# HS-Treiber.net
KiCad netlist of a schematic drawn in Altium Designer
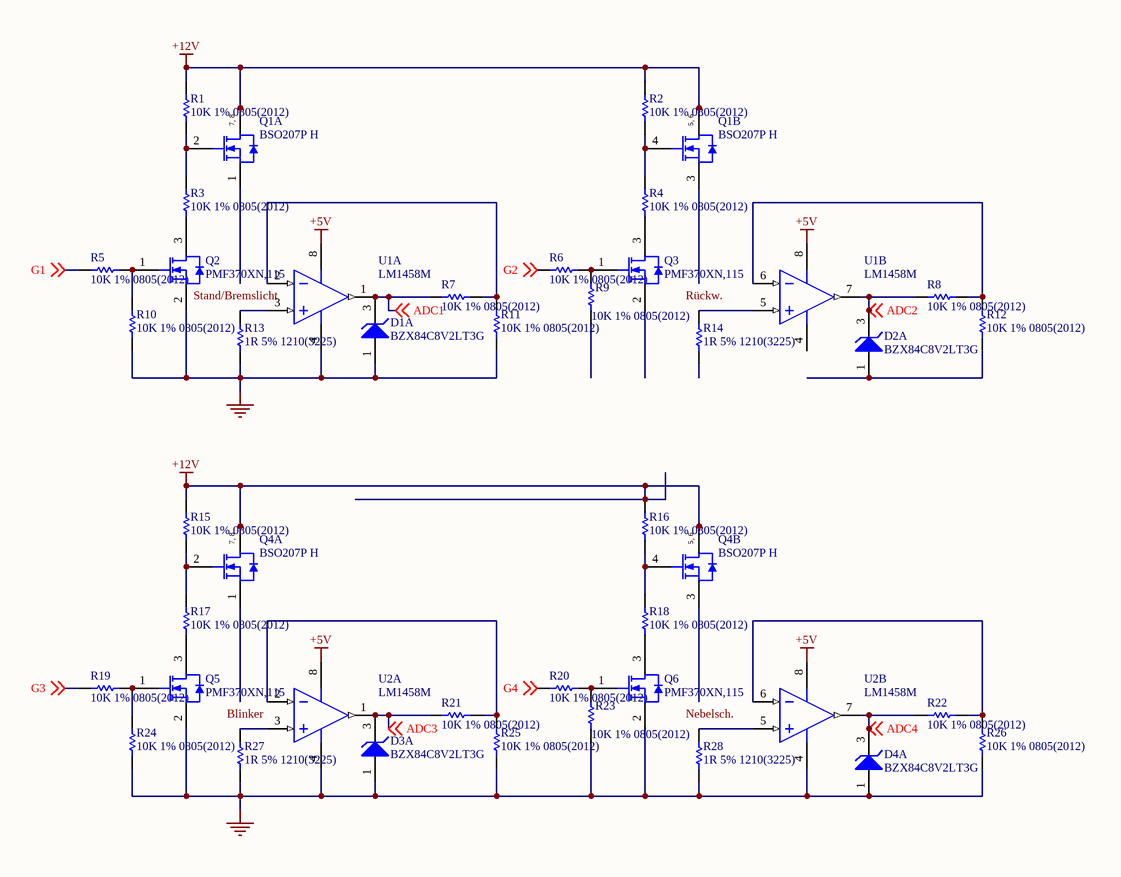
[diagram p0: HS-Treiber.SchDoc]

(export (version "E")
  (design (tool "Eeschema 10.0.6"))
  (components
    (comp (ref "D1")
      (value "BZX84C8V2LT3G")
      (footprint "ONSC-SOT-23-3-318-08_V")
      (description "Zener Voltage Regulator, 225 mW, 3-Pin SOT-23, Pb-Free, Tape and Reel")
      (fields (field (name "MANUFACTURER") "On Semiconductor"))
      (libsource (lib "Altium Content Vault") (part "ONSC-A1K3-3"))
    )
    (comp (ref "D2")
      (value "BZX84C8V2LT3G")
      (footprint "ONSC-SOT-23-3-318-08_V")
      (description "Zener Voltage Regulator, 225 mW, 3-Pin SOT-23, Pb-Free, Tape and Reel")
      (fields (field (name "MANUFACTURER") "On Semiconductor"))
      (libsource (lib "Altium Content Vault") (part "ONSC-A1K3-3"))
    )
    (comp (ref "D3")
      (value "BZX84C8V2LT3G")
      (footprint "ONSC-SOT-23-3-318-08_V")
      (description "Zener Voltage Regulator, 225 mW, 3-Pin SOT-23, Pb-Free, Tape and Reel")
      (fields (field (name "MANUFACTURER") "On Semiconductor"))
      (libsource (lib "Altium Content Vault") (part "ONSC-A1K3-3"))
    )
    (comp (ref "D4")
      (value "BZX84C8V2LT3G")
      (footprint "ONSC-SOT-23-3-318-08_V")
      (description "Zener Voltage Regulator, 225 mW, 3-Pin SOT-23, Pb-Free, Tape and Reel")
      (fields (field (name "MANUFACTURER") "On Semiconductor"))
      (libsource (lib "Altium Content Vault") (part "ONSC-A1K3-3"))
    )
    (comp (ref "Q1")
      (value "BSO207P H")
      (footprint "INF-PG-DSO-8-3_L")
      (fields (field (name "MANUFACTURER") "Infineon"))
      (libsource (lib "Altium Content Vault") (part "INF-MOS-BSXXX-8"))
    )
    (comp (ref "Q2")
      (value "PMF370XN,115")
      (footprint "NXP-SOT323_M")
      (description "N-Channel TrenchMOS Extremely Low Level FET, 30 V, 0.87 A, 3-Pin SOT323, Tape and Reel")
      (fields (field (name "MANUFACTURER") "NXP Semiconductors"))
      (libsource (lib "Altium Content Vault") (part "NXP-NMOS-GSD-3_B"))
    )
    (comp (ref "Q3")
      (value "PMF370XN,115")
      (footprint "NXP-SOT323_M")
      (description "N-Channel TrenchMOS Extremely Low Level FET, 30 V, 0.87 A, 3-Pin SOT323, Tape and Reel")
      (fields (field (name "MANUFACTURER") "NXP Semiconductors"))
      (libsource (lib "Altium Content Vault") (part "NXP-NMOS-GSD-3_B"))
    )
    (comp (ref "Q4")
      (value "BSO207P H")
      (footprint "INF-PG-DSO-8-3_L")
      (fields (field (name "MANUFACTURER") "Infineon"))
      (libsource (lib "Altium Content Vault") (part "INF-MOS-BSXXX-8"))
    )
    (comp (ref "Q5")
      (value "PMF370XN,115")
      (footprint "NXP-SOT323_M")
      (description "N-Channel TrenchMOS Extremely Low Level FET, 30 V, 0.87 A, 3-Pin SOT323, Tape and Reel")
      (fields (field (name "MANUFACTURER") "NXP Semiconductors"))
      (libsource (lib "Altium Content Vault") (part "NXP-NMOS-GSD-3_B"))
    )
    (comp (ref "Q6")
      (value "PMF370XN,115")
      (footprint "NXP-SOT323_M")
      (description "N-Channel TrenchMOS Extremely Low Level FET, 30 V, 0.87 A, 3-Pin SOT323, Tape and Reel")
      (fields (field (name "MANUFACTURER") "NXP Semiconductors"))
      (libsource (lib "Altium Content Vault") (part "NXP-NMOS-GSD-3_B"))
    )
    (comp (ref "R1")
      (value "10K 1% 0805(2012)")
      (footprint "RESC0805(2012)_M")
      (description "10K 0.125W 1% 0805 (2012 Metric)  SMD")
      (fields (field (name "TOLERANCE") "1 %") (field (name "POWER") "0.125 W"))
      (libsource (lib "Altium Content Vault") (part "RES"))
    )
    (comp (ref "R2")
      (value "10K 1% 0805(2012)")
      (footprint "RESC0805(2012)_M")
      (description "10K 0.125W 1% 0805 (2012 Metric)  SMD")
      (fields (field (name "TOLERANCE") "1 %") (field (name "POWER") "0.125 W"))
      (libsource (lib "Altium Content Vault") (part "RES"))
    )
    (comp (ref "R3")
      (value "10K 1% 0805(2012)")
      (footprint "RESC0805(2012)_M")
      (description "10K 0.125W 1% 0805 (2012 Metric)  SMD")
      (fields (field (name "TOLERANCE") "1 %") (field (name "POWER") "0.125 W"))
      (libsource (lib "Altium Content Vault") (part "RES"))
    )
    (comp (ref "R4")
      (value "10K 1% 0805(2012)")
      (footprint "RESC0805(2012)_M")
      (description "10K 0.125W 1% 0805 (2012 Metric)  SMD")
      (fields (field (name "TOLERANCE") "1 %") (field (name "POWER") "0.125 W"))
      (libsource (lib "Altium Content Vault") (part "RES"))
    )
    (comp (ref "R5")
      (value "10K 1% 0805(2012)")
      (footprint "RESC0805(2012)_M")
      (description "10K 0.125W 1% 0805 (2012 Metric)  SMD")
      (fields (field (name "TOLERANCE") "1 %") (field (name "POWER") "0.125 W"))
      (libsource (lib "Altium Content Vault") (part "RES"))
    )
    (comp (ref "R6")
      (value "10K 1% 0805(2012)")
      (footprint "RESC0805(2012)_M")
      (description "10K 0.125W 1% 0805 (2012 Metric)  SMD")
      (fields (field (name "TOLERANCE") "1 %") (field (name "POWER") "0.125 W"))
      (libsource (lib "Altium Content Vault") (part "RES"))
    )
    (comp (ref "R7")
      (value "10K 1% 0805(2012)")
      (footprint "RESC0805(2012)_M")
      (description "10K 0.125W 1% 0805 (2012 Metric)  SMD")
      (fields (field (name "TOLERANCE") "1 %") (field (name "POWER") "0.125 W"))
      (libsource (lib "Altium Content Vault") (part "RES"))
    )
    (comp (ref "R8")
      (value "10K 1% 0805(2012)")
      (footprint "RESC0805(2012)_M")
      (description "10K 0.125W 1% 0805 (2012 Metric)  SMD")
      (fields (field (name "TOLERANCE") "1 %") (field (name "POWER") "0.125 W"))
      (libsource (lib "Altium Content Vault") (part "RES"))
    )
    (comp (ref "R9")
      (value "10K 1% 0805(2012)")
      (footprint "RESC0805(2012)_M")
      (description "10K 0.125W 1% 0805 (2012 Metric)  SMD")
      (fields (field (name "TOLERANCE") "1 %") (field (name "POWER") "0.125 W"))
      (libsource (lib "Altium Content Vault") (part "RES"))
    )
    (comp (ref "R10")
      (value "10K 1% 0805(2012)")
      (footprint "RESC0805(2012)_M")
      (description "10K 0.125W 1% 0805 (2012 Metric)  SMD")
      (fields (field (name "TOLERANCE") "1 %") (field (name "POWER") "0.125 W"))
      (libsource (lib "Altium Content Vault") (part "RES"))
    )
    (comp (ref "R11")
      (value "10K 1% 0805(2012)")
      (footprint "RESC0805(2012)_M")
      (description "10K 0.125W 1% 0805 (2012 Metric)  SMD")
      (fields (field (name "TOLERANCE") "1 %") (field (name "POWER") "0.125 W"))
      (libsource (lib "Altium Content Vault") (part "RES"))
    )
    (comp (ref "R12")
      (value "10K 1% 0805(2012)")
      (footprint "RESC0805(2012)_M")
      (description "10K 0.125W 1% 0805 (2012 Metric)  SMD")
      (fields (field (name "TOLERANCE") "1 %") (field (name "POWER") "0.125 W"))
      (libsource (lib "Altium Content Vault") (part "RES"))
    )
    (comp (ref "R13")
      (value "1R 5% 1210(3225)")
      (footprint "RESC1210(3225)_N")
      (description "1R 0.5W 5% 1210 (3225 Metric)  SMD")
      (fields (field (name "POWER") "0.5 W") (field (name "TOLERANCE") "5 %"))
      (libsource (lib "Altium Content Vault") (part "RES"))
    )
    (comp (ref "R14")
      (value "1R 5% 1210(3225)")
      (footprint "RESC1210(3225)_N")
      (description "1R 0.5W 5% 1210 (3225 Metric)  SMD")
      (fields (field (name "POWER") "0.5 W") (field (name "TOLERANCE") "5 %"))
      (libsource (lib "Altium Content Vault") (part "RES"))
    )
    (comp (ref "R15")
      (value "10K 1% 0805(2012)")
      (footprint "RESC0805(2012)_M")
      (description "10K 0.125W 1% 0805 (2012 Metric)  SMD")
      (fields (field (name "TOLERANCE") "1 %") (field (name "POWER") "0.125 W"))
      (libsource (lib "Altium Content Vault") (part "RES"))
    )
    (comp (ref "R16")
      (value "10K 1% 0805(2012)")
      (footprint "RESC0805(2012)_M")
      (description "10K 0.125W 1% 0805 (2012 Metric)  SMD")
      (fields (field (name "TOLERANCE") "1 %") (field (name "POWER") "0.125 W"))
      (libsource (lib "Altium Content Vault") (part "RES"))
    )
    (comp (ref "R17")
      (value "10K 1% 0805(2012)")
      (footprint "RESC0805(2012)_M")
      (description "10K 0.125W 1% 0805 (2012 Metric)  SMD")
      (fields (field (name "TOLERANCE") "1 %") (field (name "POWER") "0.125 W"))
      (libsource (lib "Altium Content Vault") (part "RES"))
    )
    (comp (ref "R18")
      (value "10K 1% 0805(2012)")
      (footprint "RESC0805(2012)_M")
      (description "10K 0.125W 1% 0805 (2012 Metric)  SMD")
      (fields (field (name "TOLERANCE") "1 %") (field (name "POWER") "0.125 W"))
      (libsource (lib "Altium Content Vault") (part "RES"))
    )
    (comp (ref "R19")
      (value "10K 1% 0805(2012)")
      (footprint "RESC0805(2012)_M")
      (description "10K 0.125W 1% 0805 (2012 Metric)  SMD")
      (fields (field (name "TOLERANCE") "1 %") (field (name "POWER") "0.125 W"))
      (libsource (lib "Altium Content Vault") (part "RES"))
    )
    (comp (ref "R20")
      (value "10K 1% 0805(2012)")
      (footprint "RESC0805(2012)_M")
      (description "10K 0.125W 1% 0805 (2012 Metric)  SMD")
      (fields (field (name "TOLERANCE") "1 %") (field (name "POWER") "0.125 W"))
      (libsource (lib "Altium Content Vault") (part "RES"))
    )
    (comp (ref "R21")
      (value "10K 1% 0805(2012)")
      (footprint "RESC0805(2012)_M")
      (description "10K 0.125W 1% 0805 (2012 Metric)  SMD")
      (fields (field (name "TOLERANCE") "1 %") (field (name "POWER") "0.125 W"))
      (libsource (lib "Altium Content Vault") (part "RES"))
    )
    (comp (ref "R22")
      (value "10K 1% 0805(2012)")
      (footprint "RESC0805(2012)_M")
      (description "10K 0.125W 1% 0805 (2012 Metric)  SMD")
      (fields (field (name "TOLERANCE") "1 %") (field (name "POWER") "0.125 W"))
      (libsource (lib "Altium Content Vault") (part "RES"))
    )
    (comp (ref "R23")
      (value "10K 1% 0805(2012)")
      (footprint "RESC0805(2012)_M")
      (description "10K 0.125W 1% 0805 (2012 Metric)  SMD")
      (fields (field (name "TOLERANCE") "1 %") (field (name "POWER") "0.125 W"))
      (libsource (lib "Altium Content Vault") (part "RES"))
    )
    (comp (ref "R24")
      (value "10K 1% 0805(2012)")
      (footprint "RESC0805(2012)_M")
      (description "10K 0.125W 1% 0805 (2012 Metric)  SMD")
      (fields (field (name "TOLERANCE") "1 %") (field (name "POWER") "0.125 W"))
      (libsource (lib "Altium Content Vault") (part "RES"))
    )
    (comp (ref "R25")
      (value "10K 1% 0805(2012)")
      (footprint "RESC0805(2012)_M")
      (description "10K 0.125W 1% 0805 (2012 Metric)  SMD")
      (fields (field (name "TOLERANCE") "1 %") (field (name "POWER") "0.125 W"))
      (libsource (lib "Altium Content Vault") (part "RES"))
    )
    (comp (ref "R26")
      (value "10K 1% 0805(2012)")
      (footprint "RESC0805(2012)_M")
      (description "10K 0.125W 1% 0805 (2012 Metric)  SMD")
      (fields (field (name "TOLERANCE") "1 %") (field (name "POWER") "0.125 W"))
      (libsource (lib "Altium Content Vault") (part "RES"))
    )
    (comp (ref "R27")
      (value "1R 5% 1210(3225)")
      (footprint "RESC1210(3225)_N")
      (description "1R 0.5W 5% 1210 (3225 Metric)  SMD")
      (fields (field (name "POWER") "0.5 W") (field (name "TOLERANCE") "5 %"))
      (libsource (lib "Altium Content Vault") (part "RES"))
    )
    (comp (ref "R28")
      (value "1R 5% 1210(3225)")
      (footprint "RESC1210(3225)_N")
      (description "1R 0.5W 5% 1210 (3225 Metric)  SMD")
      (fields (field (name "POWER") "0.5 W") (field (name "TOLERANCE") "5 %"))
      (libsource (lib "Altium Content Vault") (part "RES"))
    )
    (comp (ref "U1")
      (value "LM1458M")
      (footprint "M08A_L")
      (description "Dual Operational Amplifier, 8-pin Narrow SOIC")
      (fields (field (name "MANUFACTURER") "National Semiconductor"))
      (libsource (lib "Altium Content Vault") (part "AMP-OPA-LF353-8"))
    )
    (comp (ref "U2")
      (value "LM1458M")
      (footprint "M08A_L")
      (description "Dual Operational Amplifier, 8-pin Narrow SOIC")
      (fields (field (name "MANUFACTURER") "National Semiconductor"))
      (libsource (lib "Altium Content Vault") (part "AMP-OPA-LF353-8"))
    )
  )
  (nets
    (net (code "1") (name "+5V") (class "Default")
      (node (ref "U1") (pin "8") (pinfunction "V+_8") (pintype "power_in"))
      (node (ref "U2") (pin "8") (pinfunction "V+_8") (pintype "power_in"))
    )
    (net (code "2") (name "+12V") (class "Default")
      (node (ref "Q1") (pin "5") (pinfunction "D2_5") (pintype "passive"))
      (node (ref "Q1") (pin "6") (pinfunction "D2_6") (pintype "passive"))
      (node (ref "Q1") (pin "7") (pinfunction "D1_7") (pintype "passive"))
      (node (ref "Q1") (pin "8") (pinfunction "D1_8") (pintype "passive"))
      (node (ref "Q4") (pin "5") (pinfunction "D2_5") (pintype "passive"))
      (node (ref "Q4") (pin "6") (pinfunction "D2_6") (pintype "passive"))
      (node (ref "Q4") (pin "7") (pinfunction "D1_7") (pintype "passive"))
      (node (ref "Q4") (pin "8") (pinfunction "D1_8") (pintype "passive"))
      (node (ref "R1") (pin "1") (pinfunction "1_1") (pintype "passive"))
      (node (ref "R15") (pin "1") (pinfunction "1_1") (pintype "passive"))
      (node (ref "R16") (pin "1") (pinfunction "1_1") (pintype "passive"))
      (node (ref "R2") (pin "1") (pinfunction "1_1") (pintype "passive"))
    )
    (net (code "3") (name "ADC1") (class "Default")
      (node (ref "D1") (pin "3") (pinfunction "K_3") (pintype "passive"))
      (node (ref "R7") (pin "1") (pinfunction "1_1") (pintype "passive"))
      (node (ref "U1") (pin "1") (pinfunction "OUTA_1") (pintype "output"))
    )
    (net (code "4") (name "ADC2") (class "Default")
      (node (ref "D2") (pin "3") (pinfunction "K_3") (pintype "passive"))
      (node (ref "R8") (pin "2") (pinfunction "2_2") (pintype "passive"))
      (node (ref "U1") (pin "7") (pinfunction "OUTB_7") (pintype "output"))
    )
    (net (code "5") (name "ADC3") (class "Default")
      (node (ref "D3") (pin "3") (pinfunction "K_3") (pintype "passive"))
      (node (ref "R21") (pin "1") (pinfunction "1_1") (pintype "passive"))
      (node (ref "U2") (pin "1") (pinfunction "OUTA_1") (pintype "output"))
    )
    (net (code "6") (name "ADC4") (class "Default")
      (node (ref "D4") (pin "3") (pinfunction "K_3") (pintype "passive"))
      (node (ref "R22") (pin "2") (pinfunction "2_2") (pintype "passive"))
      (node (ref "U2") (pin "7") (pinfunction "OUTB_7") (pintype "output"))
    )
    (net (code "7") (name "G1") (class "Default")
      (node (ref "R5") (pin "2") (pinfunction "2_2") (pintype "passive"))
    )
    (net (code "8") (name "G2") (class "Default")
      (node (ref "R6") (pin "2") (pinfunction "2_2") (pintype "passive"))
    )
    (net (code "9") (name "G3") (class "Default")
      (node (ref "R19") (pin "2") (pinfunction "2_2") (pintype "passive"))
    )
    (net (code "10") (name "G4") (class "Default")
      (node (ref "R20") (pin "2") (pinfunction "2_2") (pintype "passive"))
    )
    (net (code "11") (name "GND") (class "Default")
      (node (ref "D1") (pin "1") (pinfunction "A_1") (pintype "passive"))
      (node (ref "D3") (pin "1") (pinfunction "A_1") (pintype "passive"))
      (node (ref "D4") (pin "1") (pinfunction "A_1") (pintype "passive"))
      (node (ref "Q2") (pin "2") (pinfunction "S_2") (pintype "passive"))
      (node (ref "Q5") (pin "2") (pinfunction "S_2") (pintype "passive"))
      (node (ref "Q6") (pin "2") (pinfunction "S_2") (pintype "passive"))
      (node (ref "R10") (pin "2") (pinfunction "2_2") (pintype "passive"))
      (node (ref "R11") (pin "2") (pinfunction "2_2") (pintype "passive"))
      (node (ref "R13") (pin "2") (pinfunction "2_2") (pintype "passive"))
      (node (ref "R23") (pin "2") (pinfunction "2_2") (pintype "passive"))
      (node (ref "R24") (pin "2") (pinfunction "2_2") (pintype "passive"))
      (node (ref "R25") (pin "2") (pinfunction "2_2") (pintype "passive"))
      (node (ref "R26") (pin "2") (pinfunction "2_2") (pintype "passive"))
      (node (ref "R27") (pin "2") (pinfunction "2_2") (pintype "passive"))
      (node (ref "R28") (pin "2") (pinfunction "2_2") (pintype "passive"))
      (node (ref "U1") (pin "4") (pinfunction "V-_4") (pintype "power_in"))
      (node (ref "U2") (pin "4") (pinfunction "V-_4") (pintype "power_in"))
    )
    (net (code "12") (name "Net-(D2A-A)") (class "Default")
      (node (ref "D2") (pin "1") (pinfunction "A_1") (pintype "passive"))
      (node (ref "R12") (pin "2") (pinfunction "2_2") (pintype "passive"))
    )
    (net (code "13") (name "Net-(Q1A-G1)") (class "Default")
      (node (ref "Q1") (pin "2") (pinfunction "G1_2") (pintype "passive"))
      (node (ref "R1") (pin "2") (pinfunction "2_2") (pintype "passive"))
      (node (ref "R3") (pin "1") (pinfunction "1_1") (pintype "passive"))
    )
    (net (code "14") (name "Net-(Q1B-G2)") (class "Default")
      (node (ref "Q1") (pin "4") (pinfunction "G2_4") (pintype "passive"))
      (node (ref "R2") (pin "2") (pinfunction "2_2") (pintype "passive"))
      (node (ref "R4") (pin "1") (pinfunction "1_1") (pintype "passive"))
    )
    (net (code "15") (name "Net-(Q2-D)") (class "Default")
      (node (ref "Q2") (pin "3") (pinfunction "D_3") (pintype "passive"))
      (node (ref "R3") (pin "2") (pinfunction "2_2") (pintype "passive"))
    )
    (net (code "16") (name "Net-(Q2-G)") (class "Default")
      (node (ref "Q2") (pin "1") (pinfunction "G_1") (pintype "passive"))
      (node (ref "R10") (pin "1") (pinfunction "1_1") (pintype "passive"))
      (node (ref "R5") (pin "1") (pinfunction "1_1") (pintype "passive"))
    )
    (net (code "17") (name "Net-(Q3-D)") (class "Default")
      (node (ref "Q3") (pin "3") (pinfunction "D_3") (pintype "passive"))
      (node (ref "R4") (pin "2") (pinfunction "2_2") (pintype "passive"))
    )
    (net (code "18") (name "Net-(Q3-G)") (class "Default")
      (node (ref "Q3") (pin "1") (pinfunction "G_1") (pintype "passive"))
      (node (ref "R6") (pin "1") (pinfunction "1_1") (pintype "passive"))
      (node (ref "R9") (pin "1") (pinfunction "1_1") (pintype "passive"))
    )
    (net (code "19") (name "Net-(Q4A-G1)") (class "Default")
      (node (ref "Q4") (pin "2") (pinfunction "G1_2") (pintype "passive"))
      (node (ref "R15") (pin "2") (pinfunction "2_2") (pintype "passive"))
      (node (ref "R17") (pin "1") (pinfunction "1_1") (pintype "passive"))
    )
    (net (code "20") (name "Net-(Q4B-G2)") (class "Default")
      (node (ref "Q4") (pin "4") (pinfunction "G2_4") (pintype "passive"))
      (node (ref "R16") (pin "2") (pinfunction "2_2") (pintype "passive"))
      (node (ref "R18") (pin "1") (pinfunction "1_1") (pintype "passive"))
    )
    (net (code "21") (name "Net-(Q5-D)") (class "Default")
      (node (ref "Q5") (pin "3") (pinfunction "D_3") (pintype "passive"))
      (node (ref "R17") (pin "2") (pinfunction "2_2") (pintype "passive"))
    )
    (net (code "22") (name "Net-(Q5-G)") (class "Default")
      (node (ref "Q5") (pin "1") (pinfunction "G_1") (pintype "passive"))
      (node (ref "R19") (pin "1") (pinfunction "1_1") (pintype "passive"))
      (node (ref "R24") (pin "1") (pinfunction "1_1") (pintype "passive"))
    )
    (net (code "23") (name "Net-(Q6-D)") (class "Default")
      (node (ref "Q6") (pin "3") (pinfunction "D_3") (pintype "passive"))
      (node (ref "R18") (pin "2") (pinfunction "2_2") (pintype "passive"))
    )
    (net (code "24") (name "Net-(Q6-G)") (class "Default")
      (node (ref "Q6") (pin "1") (pinfunction "G_1") (pintype "passive"))
      (node (ref "R20") (pin "1") (pinfunction "1_1") (pintype "passive"))
      (node (ref "R23") (pin "1") (pinfunction "1_1") (pintype "passive"))
    )
    (net (code "25") (name "Net-(U1A-INA+)") (class "Default")
      (node (ref "R13") (pin "1") (pinfunction "1_1") (pintype "passive"))
      (node (ref "U1") (pin "3") (pinfunction "INA+_3") (pintype "input"))
    )
    (net (code "26") (name "Net-(U1A-INA-)") (class "Default")
      (node (ref "R11") (pin "1") (pinfunction "1_1") (pintype "passive"))
      (node (ref "R7") (pin "2") (pinfunction "2_2") (pintype "passive"))
      (node (ref "U1") (pin "2") (pinfunction "INA-_2") (pintype "input"))
    )
    (net (code "27") (name "Net-(U1B-INB+)") (class "Default")
      (node (ref "R14") (pin "1") (pinfunction "1_1") (pintype "passive"))
      (node (ref "U1") (pin "5") (pinfunction "INB+_5") (pintype "input"))
    )
    (net (code "28") (name "Net-(U1B-INB-)") (class "Default")
      (node (ref "R12") (pin "1") (pinfunction "1_1") (pintype "passive"))
      (node (ref "R8") (pin "1") (pinfunction "1_1") (pintype "passive"))
      (node (ref "U1") (pin "6") (pinfunction "INB-_6") (pintype "input"))
    )
    (net (code "29") (name "Net-(U2A-INA+)") (class "Default")
      (node (ref "R27") (pin "1") (pinfunction "1_1") (pintype "passive"))
      (node (ref "U2") (pin "3") (pinfunction "INA+_3") (pintype "input"))
    )
    (net (code "30") (name "Net-(U2A-INA-)") (class "Default")
      (node (ref "R21") (pin "2") (pinfunction "2_2") (pintype "passive"))
      (node (ref "R25") (pin "1") (pinfunction "1_1") (pintype "passive"))
      (node (ref "U2") (pin "2") (pinfunction "INA-_2") (pintype "input"))
    )
    (net (code "31") (name "Net-(U2B-INB+)") (class "Default")
      (node (ref "R28") (pin "1") (pinfunction "1_1") (pintype "passive"))
      (node (ref "U2") (pin "5") (pinfunction "INB+_5") (pintype "input"))
    )
    (net (code "32") (name "Net-(U2B-INB-)") (class "Default")
      (node (ref "R22") (pin "1") (pinfunction "1_1") (pintype "passive"))
      (node (ref "R26") (pin "1") (pinfunction "1_1") (pintype "passive"))
      (node (ref "U2") (pin "6") (pinfunction "INB-_6") (pintype "input"))
    )
    (net (code "33") (name "unconnected-(Q1A-S1-Pad1)") (class "Default")
      (node (ref "Q1") (pin "1") (pinfunction "S1_1") (pintype "passive"))
    )
    (net (code "34") (name "unconnected-(Q1B-S2-Pad3)") (class "Default")
      (node (ref "Q1") (pin "3") (pinfunction "S2_3") (pintype "passive"))
    )
    (net (code "35") (name "unconnected-(Q3-S-Pad2)") (class "Default")
      (node (ref "Q3") (pin "2") (pinfunction "S_2") (pintype "passive"))
    )
    (net (code "36") (name "unconnected-(Q4A-S1-Pad1)") (class "Default")
      (node (ref "Q4") (pin "1") (pinfunction "S1_1") (pintype "passive"))
    )
    (net (code "37") (name "unconnected-(Q4B-S2-Pad3)") (class "Default")
      (node (ref "Q4") (pin "3") (pinfunction "S2_3") (pintype "passive"))
    )
    (net (code "38") (name "unconnected-(R9-Pad2)") (class "Default")
      (node (ref "R9") (pin "2") (pinfunction "2_2") (pintype "passive"))
    )
    (net (code "39") (name "unconnected-(R14-Pad2)") (class "Default")
      (node (ref "R14") (pin "2") (pinfunction "2_2") (pintype "passive"))
    )
    (net (code "40") (name "unconnected-(U1B-V--Pad4)") (class "Default")
      (node (ref "U1") (pin "4") (pinfunction "V-_4") (pintype "power_in"))
    )
  )
)
